# XR1.net
KiCad netlist of a schematic drawn in EAGLE
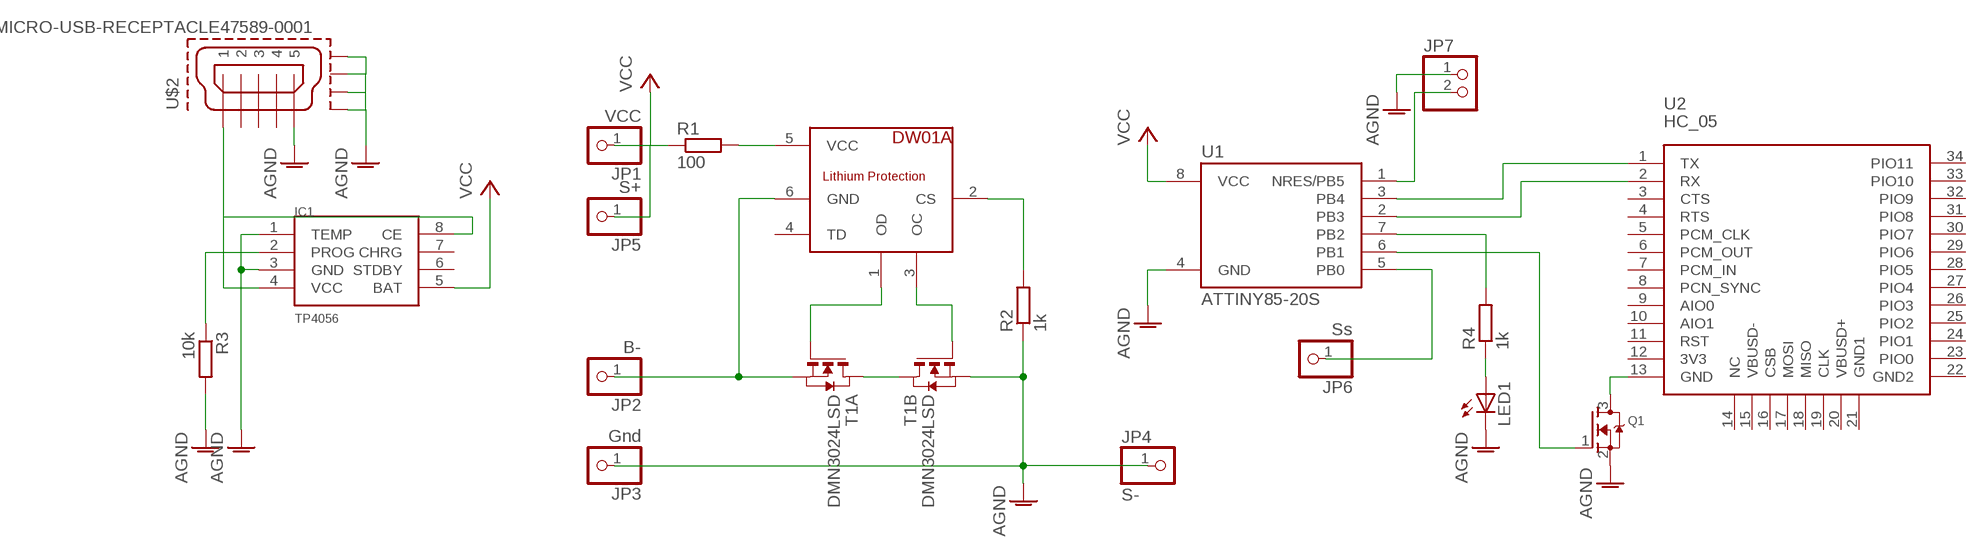
[diagram p0: schematic, sheet 1]

(export (version "E")
  (design (tool "Eeschema 10.0.6"))
  (components
    (comp (ref "IC1")
      (value "TP4056")
      (footprint "eagle-import:SOP-8")
      (libsource (lib "eagle-import") (part "TP4056"))
    )
    (comp (ref "JP1")
      (value "VCC")
      (footprint "eagle-import:1X01")
      (libsource (lib "eagle-import") (part "PINHD-1X1"))
    )
    (comp (ref "JP2")
      (value "B-")
      (footprint "eagle-import:1X01")
      (libsource (lib "eagle-import") (part "PINHD-1X1"))
    )
    (comp (ref "JP3")
      (value "Gnd")
      (footprint "eagle-import:1X01")
      (libsource (lib "eagle-import") (part "PINHD-1X1"))
    )
    (comp (ref "JP4")
      (value "S-")
      (footprint "eagle-import:1X01")
      (libsource (lib "eagle-import") (part "PINHD-1X1"))
    )
    (comp (ref "JP5")
      (value "S+")
      (footprint "eagle-import:1X01")
      (libsource (lib "eagle-import") (part "PINHD-1X1"))
    )
    (comp (ref "JP6")
      (value "Ss")
      (footprint "eagle-import:1X01")
      (libsource (lib "eagle-import") (part "PINHD-1X1"))
    )
    (comp (ref "JP7")
      (value "PINHD-1X2")
      (footprint "eagle-import:1X02")
      (libsource (lib "eagle-import") (part "PINHD-1X2"))
    )
    (comp (ref "LED1")
      (value "LEDCHIP-LED0603")
      (footprint "eagle-import:CHIP-LED0603")
      (libsource (lib "eagle-import") (part "LEDCHIP-LED0603"))
    )
    (comp (ref "Q1")
      (value "MOSFET-NREFLOW")
      (footprint "eagle-import:SOT23")
      (libsource (lib "eagle-import") (part "MOSFET-NREFLOW"))
    )
    (comp (ref "R1")
      (value "100")
      (footprint "eagle-import:R0603")
      (libsource (lib "eagle-import") (part "R-EU_R0603"))
    )
    (comp (ref "R2")
      (value "1k")
      (footprint "eagle-import:R0603")
      (libsource (lib "eagle-import") (part "R-EU_R0603"))
    )
    (comp (ref "R3")
      (value "10k")
      (footprint "eagle-import:R0603")
      (libsource (lib "eagle-import") (part "R-EU_R0603"))
    )
    (comp (ref "R4")
      (value "1k")
      (footprint "eagle-import:R0603")
      (libsource (lib "eagle-import") (part "R-EU_R0603"))
    )
    (comp (ref "T1")
      (value "DMN3024LSD")
      (footprint "eagle-import:TSSOP-8")
      (libsource (lib "eagle-import") (part "DMN3024LSD"))
    )
    (comp (ref "U$1")
      (value "DW01A")
      (footprint "eagle-import:SOT23-6")
      (libsource (lib "eagle-import") (part "DW01A"))
    )
    (comp (ref "U$2")
      (value "MICRO-USB-RECEPTACLE47589-0001")
      (footprint "eagle-import:47589-0001")
      (libsource (lib "eagle-import") (part "MICRO-USB-RECEPTACLE47589-0001"))
    )
    (comp (ref "U1")
      (value "ATTINY85-20S")
      (footprint "eagle-import:SOIC8_EIAJ_208MIL")
      (libsource (lib "eagle-import") (part "ATTINY85S-20"))
    )
    (comp (ref "U2")
      (value "HC_05")
      (footprint "eagle-import:BLUETOOTH_SMD")
      (libsource (lib "eagle-import") (part "HC_05"))
    )
  )
  (nets
    (net (code "1") (name "AGND") (class "Default")
      (node (ref "IC1") (pin "1") (pinfunction "TEMP_1") (pintype "bidirectional"))
      (node (ref "IC1") (pin "3") (pinfunction "GND_3") (pintype "bidirectional"))
      (node (ref "JP3") (pin "1") (pinfunction "1_1") (pintype "passive"))
      (node (ref "JP4") (pin "1") (pinfunction "1_1") (pintype "passive"))
      (node (ref "JP7") (pin "1") (pinfunction "1_1") (pintype "passive"))
      (node (ref "LED1") (pin "C") (pinfunction "C_C") (pintype "passive"))
      (node (ref "Q1") (pin "2") (pinfunction "S_2") (pintype "bidirectional"))
      (node (ref "R2") (pin "1") (pinfunction "1_1") (pintype "passive"))
      (node (ref "R3") (pin "2") (pinfunction "2_2") (pintype "passive"))
      (node (ref "T1") (pin "6") (pinfunction "S_6") (pintype "passive"))
      (node (ref "T1") (pin "7") (pinfunction "S_7") (pintype "passive"))
      (node (ref "U$2") (pin "5") (pinfunction "5_5") (pintype "input"))
      (node (ref "U$2") (pin "CASING1") (pinfunction "GND1_CASING1") (pintype "bidirectional"))
      (node (ref "U$2") (pin "CASING2") (pinfunction "GND2_CASING2") (pintype "bidirectional"))
      (node (ref "U$2") (pin "CASING3") (pinfunction "GND3_CASING3") (pintype "bidirectional"))
      (node (ref "U$2") (pin "CASING4") (pinfunction "GND4_CASING4") (pintype "bidirectional"))
      (node (ref "U1") (pin "4") (pinfunction "GND_4") (pintype "power_in"))
    )
    (net (code "2") (name "Net-(IC1-CE)") (class "Default")
      (node (ref "IC1") (pin "4") (pinfunction "VCC_4") (pintype "bidirectional"))
      (node (ref "IC1") (pin "8") (pinfunction "CE_8") (pintype "bidirectional"))
      (node (ref "U$2") (pin "1") (pinfunction "1_1") (pintype "input"))
    )
    (net (code "3") (name "Net-(IC1-PROG)") (class "Default")
      (node (ref "IC1") (pin "2") (pinfunction "PROG_2") (pintype "bidirectional"))
      (node (ref "R3") (pin "1") (pinfunction "1_1") (pintype "passive"))
    )
    (net (code "4") (name "Net-(LED1-PadA)") (class "Default")
      (node (ref "LED1") (pin "A") (pinfunction "A_A") (pintype "passive"))
      (node (ref "R4") (pin "1") (pinfunction "1_1") (pintype "passive"))
    )
    (net (code "5") (name "Net-(Q1-D)") (class "Default")
      (node (ref "Q1") (pin "3") (pinfunction "D_3") (pintype "bidirectional"))
      (node (ref "U2") (pin "13") (pinfunction "GND_13") (pintype "bidirectional"))
    )
    (net (code "6") (name "Net-(Q1-G)") (class "Default")
      (node (ref "Q1") (pin "1") (pinfunction "G_1") (pintype "bidirectional"))
      (node (ref "U1") (pin "6") (pinfunction "PB1_6") (pintype "bidirectional"))
    )
    (net (code "7") (name "Net-(T1A-D)") (class "Default")
      (node (ref "T1") (pin "1") (pinfunction "D_1") (pintype "passive"))
      (node (ref "T1") (pin "8") (pinfunction "D_8") (pintype "passive"))
    )
    (net (code "8") (name "Net-(T1A-G)") (class "Default")
      (node (ref "T1") (pin "4") (pinfunction "G_4") (pintype "passive"))
      (node (ref "U$1") (pin "1") (pinfunction "OD_1") (pintype "bidirectional"))
    )
    (net (code "9") (name "Net-(T1B-G)") (class "Default")
      (node (ref "T1") (pin "5") (pinfunction "G_5") (pintype "passive"))
      (node (ref "U$1") (pin "3") (pinfunction "OC_3") (pintype "bidirectional"))
    )
    (net (code "10") (name "Net-(U$1-CS)") (class "Default")
      (node (ref "R2") (pin "2") (pinfunction "2_2") (pintype "passive"))
      (node (ref "U$1") (pin "2") (pinfunction "CS_2") (pintype "bidirectional"))
    )
    (net (code "11") (name "Net-(U$1-GND)") (class "Default")
      (node (ref "JP2") (pin "1") (pinfunction "1_1") (pintype "passive"))
      (node (ref "T1") (pin "2") (pinfunction "S_2") (pintype "passive"))
      (node (ref "T1") (pin "3") (pinfunction "S_3") (pintype "passive"))
      (node (ref "U$1") (pin "6") (pinfunction "GND_6") (pintype "bidirectional"))
    )
    (net (code "12") (name "Net-(U$1-VCC)") (class "Default")
      (node (ref "R1") (pin "2") (pinfunction "2_2") (pintype "passive"))
      (node (ref "U$1") (pin "5") (pinfunction "VCC_5") (pintype "bidirectional"))
    )
    (net (code "13") (name "Net-(U1-NRES{slash}PB5)") (class "Default")
      (node (ref "JP7") (pin "2") (pinfunction "2_2") (pintype "passive"))
      (node (ref "U1") (pin "1") (pinfunction "NRES/PB5_1") (pintype "bidirectional"))
    )
    (net (code "14") (name "Net-(U1-PB0)") (class "Default")
      (node (ref "JP6") (pin "1") (pinfunction "1_1") (pintype "passive"))
      (node (ref "U1") (pin "5") (pinfunction "PB0_5") (pintype "bidirectional"))
    )
    (net (code "15") (name "Net-(U1-PB2)") (class "Default")
      (node (ref "R4") (pin "2") (pinfunction "2_2") (pintype "passive"))
      (node (ref "U1") (pin "7") (pinfunction "PB2_7") (pintype "bidirectional"))
    )
    (net (code "16") (name "Net-(U1-PB3)") (class "Default")
      (node (ref "U1") (pin "2") (pinfunction "PB3_2") (pintype "bidirectional"))
      (node (ref "U2") (pin "2") (pinfunction "RX_2") (pintype "bidirectional"))
    )
    (net (code "17") (name "Net-(U1-PB4)") (class "Default")
      (node (ref "U1") (pin "3") (pinfunction "PB4_3") (pintype "bidirectional"))
      (node (ref "U2") (pin "1") (pinfunction "TX_1") (pintype "bidirectional"))
    )
    (net (code "18") (name "VCC") (class "Default")
      (node (ref "IC1") (pin "5") (pinfunction "BAT_5") (pintype "bidirectional"))
      (node (ref "JP1") (pin "1") (pinfunction "1_1") (pintype "passive"))
      (node (ref "JP5") (pin "1") (pinfunction "1_1") (pintype "passive"))
      (node (ref "R1") (pin "1") (pinfunction "1_1") (pintype "passive"))
      (node (ref "U1") (pin "8") (pinfunction "VCC_8") (pintype "power_in"))
    )
    (net (code "19") (name "unconnected-(IC1-CHRG-Pad7)") (class "Default")
      (node (ref "IC1") (pin "7") (pinfunction "CHRG_7") (pintype "bidirectional"))
    )
    (net (code "20") (name "unconnected-(IC1-STDBY-Pad6)") (class "Default")
      (node (ref "IC1") (pin "6") (pinfunction "STDBY_6") (pintype "bidirectional"))
    )
    (net (code "21") (name "unconnected-(U$1-TD-Pad4)") (class "Default")
      (node (ref "U$1") (pin "4") (pinfunction "TD_4") (pintype "bidirectional"))
    )
    (net (code "22") (name "unconnected-(U$2-Pad2)") (class "Default")
      (node (ref "U$2") (pin "2") (pinfunction "2_2") (pintype "input"))
    )
    (net (code "23") (name "unconnected-(U$2-Pad3)") (class "Default")
      (node (ref "U$2") (pin "3") (pinfunction "3_3") (pintype "input"))
    )
    (net (code "24") (name "unconnected-(U$2-Pad4)") (class "Default")
      (node (ref "U$2") (pin "4") (pinfunction "4_4") (pintype "input"))
    )
    (net (code "25") (name "unconnected-(U2-3V3-Pad12)") (class "Default")
      (node (ref "U2") (pin "12") (pinfunction "3V3_12") (pintype "bidirectional"))
    )
    (net (code "26") (name "unconnected-(U2-AIO0-Pad9)") (class "Default")
      (node (ref "U2") (pin "9") (pinfunction "AIO0_9") (pintype "bidirectional"))
    )
    (net (code "27") (name "unconnected-(U2-AIO1-Pad10)") (class "Default")
      (node (ref "U2") (pin "10") (pinfunction "AIO1_10") (pintype "bidirectional"))
    )
    (net (code "28") (name "unconnected-(U2-CLK-Pad19)") (class "Default")
      (node (ref "U2") (pin "19") (pinfunction "CLK_19") (pintype "bidirectional"))
    )
    (net (code "29") (name "unconnected-(U2-CSB-Pad16)") (class "Default")
      (node (ref "U2") (pin "16") (pinfunction "CSB_16") (pintype "bidirectional"))
    )
    (net (code "30") (name "unconnected-(U2-CTS-Pad3)") (class "Default")
      (node (ref "U2") (pin "3") (pinfunction "CTS_3") (pintype "bidirectional"))
    )
    (net (code "31") (name "unconnected-(U2-GND1-Pad21)") (class "Default")
      (node (ref "U2") (pin "21") (pinfunction "GND1_21") (pintype "bidirectional"))
    )
    (net (code "32") (name "unconnected-(U2-GND2-Pad22)") (class "Default")
      (node (ref "U2") (pin "22") (pinfunction "GND2_22") (pintype "bidirectional"))
    )
    (net (code "33") (name "unconnected-(U2-MISO-Pad18)") (class "Default")
      (node (ref "U2") (pin "18") (pinfunction "MISO_18") (pintype "bidirectional"))
    )
    (net (code "34") (name "unconnected-(U2-MOSI-Pad17)") (class "Default")
      (node (ref "U2") (pin "17") (pinfunction "MOSI_17") (pintype "bidirectional"))
    )
    (net (code "35") (name "unconnected-(U2-NC-Pad14)") (class "Default")
      (node (ref "U2") (pin "14") (pinfunction "NC_14") (pintype "bidirectional"))
    )
    (net (code "36") (name "unconnected-(U2-PCM_CLK-Pad5)") (class "Default")
      (node (ref "U2") (pin "5") (pinfunction "PCM_CLK_5") (pintype "bidirectional"))
    )
    (net (code "37") (name "unconnected-(U2-PCM_IN-Pad7)") (class "Default")
      (node (ref "U2") (pin "7") (pinfunction "PCM_IN_7") (pintype "bidirectional"))
    )
    (net (code "38") (name "unconnected-(U2-PCM_OUT-Pad6)") (class "Default")
      (node (ref "U2") (pin "6") (pinfunction "PCM_OUT_6") (pintype "bidirectional"))
    )
    (net (code "39") (name "unconnected-(U2-PCN_SYNC-Pad8)") (class "Default")
      (node (ref "U2") (pin "8") (pinfunction "PCN_SYNC_8") (pintype "bidirectional"))
    )
    (net (code "40") (name "unconnected-(U2-PIO0-Pad23)") (class "Default")
      (node (ref "U2") (pin "23") (pinfunction "PIO0_23") (pintype "bidirectional"))
    )
    (net (code "41") (name "unconnected-(U2-PIO1-Pad24)") (class "Default")
      (node (ref "U2") (pin "24") (pinfunction "PIO1_24") (pintype "bidirectional"))
    )
    (net (code "42") (name "unconnected-(U2-PIO2-Pad25)") (class "Default")
      (node (ref "U2") (pin "25") (pinfunction "PIO2_25") (pintype "bidirectional"))
    )
    (net (code "43") (name "unconnected-(U2-PIO3-Pad26)") (class "Default")
      (node (ref "U2") (pin "26") (pinfunction "PIO3_26") (pintype "bidirectional"))
    )
    (net (code "44") (name "unconnected-(U2-PIO4-Pad27)") (class "Default")
      (node (ref "U2") (pin "27") (pinfunction "PIO4_27") (pintype "bidirectional"))
    )
    (net (code "45") (name "unconnected-(U2-PIO5-Pad28)") (class "Default")
      (node (ref "U2") (pin "28") (pinfunction "PIO5_28") (pintype "bidirectional"))
    )
    (net (code "46") (name "unconnected-(U2-PIO6-Pad29)") (class "Default")
      (node (ref "U2") (pin "29") (pinfunction "PIO6_29") (pintype "bidirectional"))
    )
    (net (code "47") (name "unconnected-(U2-PIO7-Pad30)") (class "Default")
      (node (ref "U2") (pin "30") (pinfunction "PIO7_30") (pintype "bidirectional"))
    )
    (net (code "48") (name "unconnected-(U2-PIO8-Pad31)") (class "Default")
      (node (ref "U2") (pin "31") (pinfunction "PIO8_31") (pintype "bidirectional"))
    )
    (net (code "49") (name "unconnected-(U2-PIO9-Pad32)") (class "Default")
      (node (ref "U2") (pin "32") (pinfunction "PIO9_32") (pintype "bidirectional"))
    )
    (net (code "50") (name "unconnected-(U2-PIO10-Pad33)") (class "Default")
      (node (ref "U2") (pin "33") (pinfunction "PIO10_33") (pintype "bidirectional"))
    )
    (net (code "51") (name "unconnected-(U2-PIO11-Pad34)") (class "Default")
      (node (ref "U2") (pin "34") (pinfunction "PIO11_34") (pintype "bidirectional"))
    )
    (net (code "52") (name "unconnected-(U2-RST-Pad11)") (class "Default")
      (node (ref "U2") (pin "11") (pinfunction "RST_11") (pintype "bidirectional"))
    )
    (net (code "53") (name "unconnected-(U2-RTS-Pad4)") (class "Default")
      (node (ref "U2") (pin "4") (pinfunction "RTS_4") (pintype "bidirectional"))
    )
    (net (code "54") (name "unconnected-(U2-VBUSD+-Pad20)") (class "Default")
      (node (ref "U2") (pin "20") (pinfunction "VBUSD+_20") (pintype "bidirectional"))
    )
    (net (code "55") (name "unconnected-(U2-VBUSD--Pad15)") (class "Default")
      (node (ref "U2") (pin "15") (pinfunction "VBUSD-_15") (pintype "bidirectional"))
    )
  )
)
